# Sheet1.net
KiCad netlist of a schematic drawn in Altium Designer
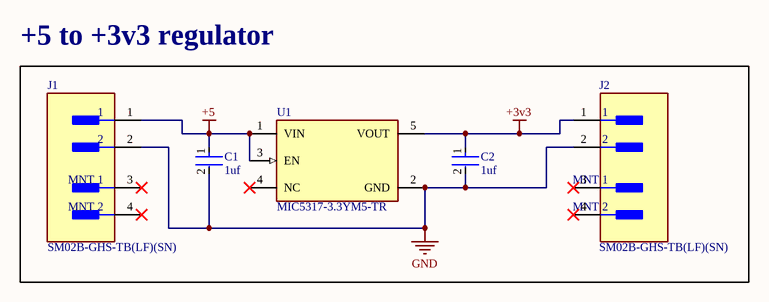
[diagram p0: Sheet1.SchDoc]

(export (version "E")
  (design (tool "Eeschema 10.0.6"))
  (components
    (comp (ref "C1")
      (value "1uf")
      (footprint "FP-CC0805-0_85-MFG")
      (description "CAP CER 1UF 10V X7R 0805")
      (fields
        (field (name "MANUFACTURER") "Yageo")
        (field (name "OCTOPART") "https://octopart.com/cc0805kkx7r6bb105-yageo-42522859")
      )
      (libsource (lib "Altium Content Vault") (part "11868f565c42a9108669ba33697ecf6"))
    )
    (comp (ref "C2")
      (value "1uf")
      (footprint "FP-CC0805-0_85-MFG")
      (description "CAP CER 1UF 10V X7R 0805")
      (fields
        (field (name "MANUFACTURER") "Yageo")
        (field (name "OCTOPART") "https://octopart.com/cc0805kkx7r6bb105-yageo-42522859")
      )
      (libsource (lib "Altium Content Vault") (part "11868f565c42a9108669ba33697ecf6"))
    )
    (comp (ref "J1")
      (value "SM02B-GHS-TB(LF)(SN)")
      (footprint "FP-SM02B-GHS-TB_LF_SN-MFG")
      (description "CONN HEADER SMD R/A 2POS 1.25MM")
      (libsource (lib "") (part "56ec3178a87b3978bdc1b3682cd516a_1"))
    )
    (comp (ref "J2")
      (value "SM02B-GHS-TB(LF)(SN)")
      (footprint "FP-SM02B-GHS-TB_LF_SN-MFG")
      (description "CONN HEADER SMD R/A 2POS 1.25MM")
      (libsource (lib "Altium Content Vault") (part "56ec3178a87b3978bdc1b3682cd516a"))
    )
    (comp (ref "U1")
      (value "MIC5317-3.3YM5-TR")
      (footprint "FP-SOT23-5LD-PL-1-MFG")
      (description "IC REG LINEAR 3.3V 150MA SOT23-5")
      (libsource (lib "Altium Content Vault") (part "0a093dae7315cdc977fd108dde87457"))
    )
  )
  (nets
    (net (code "1") (name "+3v3") (class "Default")
      (node (ref "C2") (pin "1") (pinfunction "1_1") (pintype "passive"))
      (node (ref "J2") (pin "1") (pinfunction "1_1") (pintype "passive"))
      (node (ref "U1") (pin "5") (pinfunction "VOUT_5") (pintype "power_in"))
    )
    (net (code "2") (name "+5") (class "Default")
      (node (ref "C1") (pin "1") (pinfunction "1_1") (pintype "passive"))
      (node (ref "J1") (pin "1") (pinfunction "1_1") (pintype "passive"))
      (node (ref "U1") (pin "1") (pinfunction "VIN_1") (pintype "power_in"))
      (node (ref "U1") (pin "3") (pinfunction "EN_3") (pintype "input"))
    )
    (net (code "3") (name "GND") (class "Default")
      (node (ref "C1") (pin "2") (pinfunction "2_2") (pintype "passive"))
      (node (ref "C2") (pin "2") (pinfunction "2_2") (pintype "passive"))
      (node (ref "J1") (pin "2") (pinfunction "2_2") (pintype "passive"))
      (node (ref "J2") (pin "2") (pinfunction "2_2") (pintype "passive"))
      (node (ref "U1") (pin "2") (pinfunction "GND_2") (pintype "power_in"))
    )
    (net (code "4") (name "unconnected-(J1-MNT_1-Pad3)") (class "Default")
      (node (ref "J1") (pin "3") (pinfunction "MNT_1_3") (pintype "passive+no_connect"))
    )
    (net (code "5") (name "unconnected-(J1-MNT_2-Pad4)") (class "Default")
      (node (ref "J1") (pin "4") (pinfunction "MNT_2_4") (pintype "passive+no_connect"))
    )
    (net (code "6") (name "unconnected-(J2-MNT_1-Pad3)") (class "Default")
      (node (ref "J2") (pin "3") (pinfunction "MNT_1_3") (pintype "passive+no_connect"))
    )
    (net (code "7") (name "unconnected-(J2-MNT_2-Pad4)") (class "Default")
      (node (ref "J2") (pin "4") (pinfunction "MNT_2_4") (pintype "passive+no_connect"))
    )
    (net (code "8") (name "unconnected-(U1-NC-Pad4)") (class "Default")
      (node (ref "U1") (pin "4") (pinfunction "NC_4") (pintype "passive+no_connect"))
    )
  )
)
